# Mainboard_-_Prototyp_2.net
KiCad netlist of a schematic drawn in EAGLE
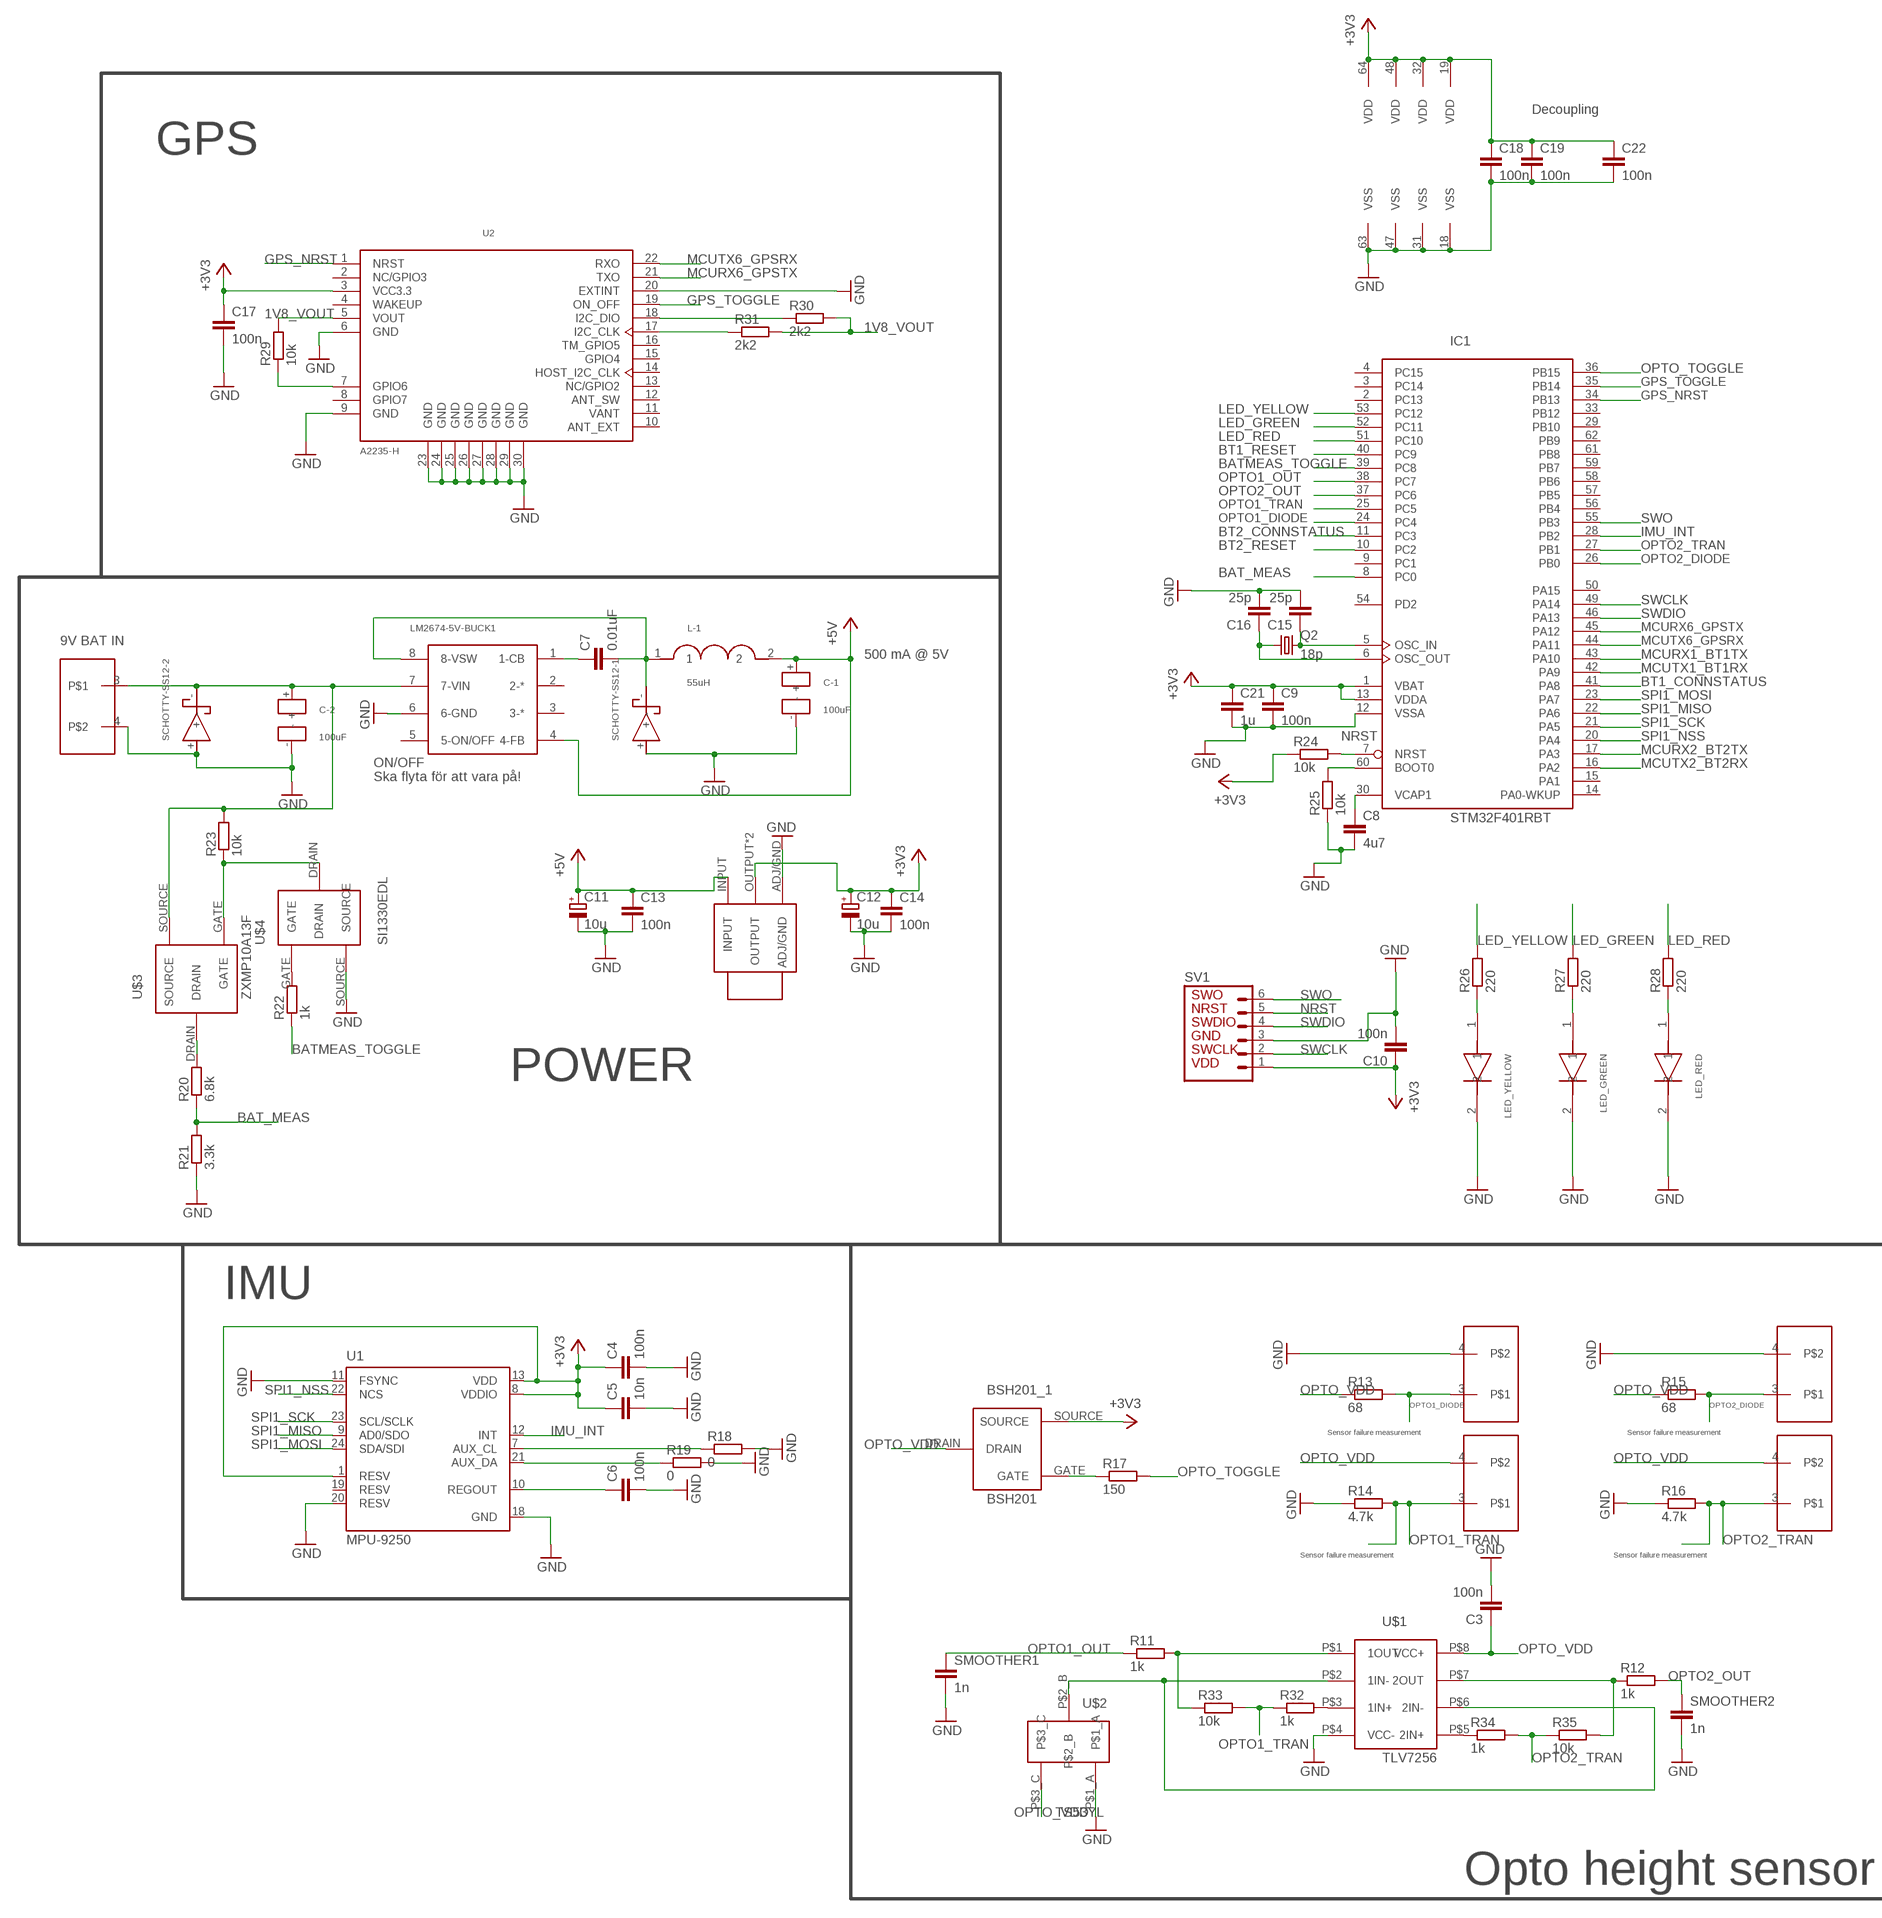
[diagram p0: schematic, sheet 1, part 1 of 2]
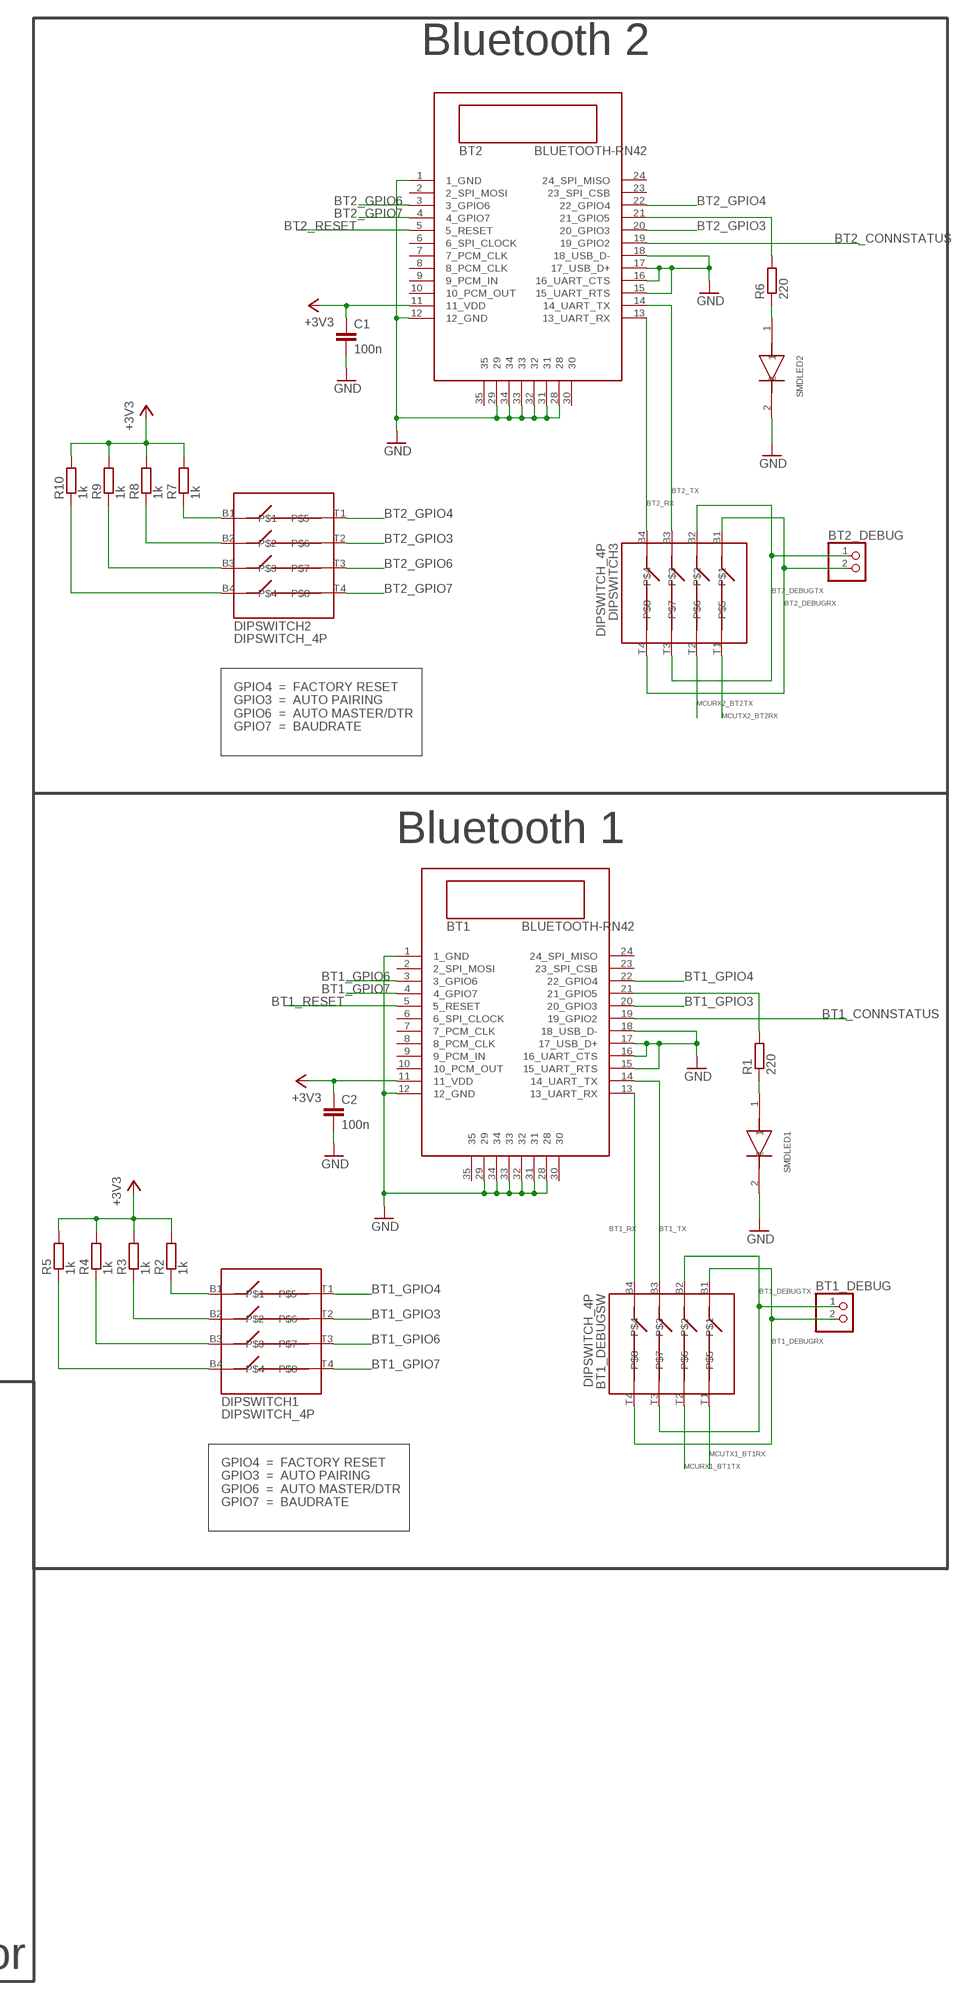
[diagram p1: schematic, sheet 1, part 2 of 2]

(export (version "E")
  (design (tool "Eeschema 10.0.6"))
  (components
    (comp (ref "BSH201_1")
      (value "BSH201")
      (footprint "eagle-import:P-CHANNEL")
      (libsource (lib "eagle-import") (part "BSH201"))
    )
    (comp (ref "BT1")
      (value "BLUETOOTH-RN42")
      (footprint "eagle-import:RN42")
      (libsource (lib "eagle-import") (part "BLUETOOTH-RN42"))
    )
    (comp (ref "BT1_DEBUG")
      (value "PINHD-1X2")
      (footprint "eagle-import:1X02")
      (libsource (lib "eagle-import") (part "PINHD-1X2"))
    )
    (comp (ref "BT1_DEBUGSW")
      (value "DIPSWITCH_4P")
      (footprint "eagle-import:DIPSWITCH4P")
      (libsource (lib "eagle-import") (part "DIPSWITCH_4P"))
    )
    (comp (ref "BT2")
      (value "BLUETOOTH-RN42")
      (footprint "eagle-import:RN42")
      (libsource (lib "eagle-import") (part "BLUETOOTH-RN42"))
    )
    (comp (ref "BT2_DEBUG")
      (value "PINHD-1X2")
      (footprint "eagle-import:1X02")
      (libsource (lib "eagle-import") (part "PINHD-1X2"))
    )
    (comp (ref "C-1")
      (value "100uF")
      (footprint "eagle-import:CAP-6.3MM-DIA")
      (libsource (lib "eagle-import") (part "PANASONIC-CAP"))
    )
    (comp (ref "C-2")
      (value "100uF")
      (footprint "eagle-import:CAP-6.3MM-DIA")
      (libsource (lib "eagle-import") (part "PANASONIC-CAP"))
    )
    (comp (ref "C1")
      (value "100n")
      (footprint "eagle-import:C0805")
      (libsource (lib "eagle-import") (part "C-EUC0805"))
    )
    (comp (ref "C2")
      (value "100n")
      (footprint "eagle-import:C0805")
      (libsource (lib "eagle-import") (part "C-EUC0805"))
    )
    (comp (ref "C3")
      (value "100n")
      (footprint "eagle-import:C0805")
      (libsource (lib "eagle-import") (part "C-EUC0805"))
    )
    (comp (ref "C4")
      (value "100n")
      (footprint "eagle-import:C0805")
      (libsource (lib "eagle-import") (part "C-EUC0805"))
    )
    (comp (ref "C5")
      (value "10n")
      (footprint "eagle-import:C0805")
      (libsource (lib "eagle-import") (part "C-EUC0805"))
    )
    (comp (ref "C6")
      (value "100n")
      (footprint "eagle-import:C0805")
      (libsource (lib "eagle-import") (part "C-EUC0805"))
    )
    (comp (ref "C7")
      (value "0.01uF")
      (footprint "eagle-import:C0805")
      (libsource (lib "eagle-import") (part "C-EUC0805"))
    )
    (comp (ref "C8")
      (value "4u7")
      (footprint "eagle-import:C0805")
      (libsource (lib "eagle-import") (part "C-EUC0805"))
    )
    (comp (ref "C9")
      (value "100n")
      (footprint "eagle-import:C0805")
      (libsource (lib "eagle-import") (part "C-EUC0805"))
    )
    (comp (ref "C10")
      (value "100n")
      (footprint "eagle-import:C0805")
      (libsource (lib "eagle-import") (part "C-EUC0805"))
    )
    (comp (ref "C11")
      (value "10u")
      (footprint "eagle-import:153CLV-0505")
      (libsource (lib "eagle-import") (part "CPOL-EU153CLV-0505"))
    )
    (comp (ref "C12")
      (value "10u")
      (footprint "eagle-import:153CLV-0505")
      (libsource (lib "eagle-import") (part "CPOL-EU153CLV-0505"))
    )
    (comp (ref "C13")
      (value "100n")
      (footprint "eagle-import:C0805")
      (libsource (lib "eagle-import") (part "C-EUC0805"))
    )
    (comp (ref "C14")
      (value "100n")
      (footprint "eagle-import:C0805")
      (libsource (lib "eagle-import") (part "C-EUC0805"))
    )
    (comp (ref "C15")
      (value "25p")
      (footprint "eagle-import:C0805")
      (libsource (lib "eagle-import") (part "C-EUC0805"))
    )
    (comp (ref "C16")
      (value "25p")
      (footprint "eagle-import:C0805")
      (libsource (lib "eagle-import") (part "C-EUC0805"))
    )
    (comp (ref "C17")
      (value "100n")
      (footprint "eagle-import:C0805")
      (libsource (lib "eagle-import") (part "C-EUC0805"))
    )
    (comp (ref "C18")
      (value "100n")
      (footprint "eagle-import:C0805")
      (libsource (lib "eagle-import") (part "C-EUC0805"))
    )
    (comp (ref "C19")
      (value "100n")
      (footprint "eagle-import:C0805")
      (libsource (lib "eagle-import") (part "C-EUC0805"))
    )
    (comp (ref "C21")
      (value "1u")
      (footprint "eagle-import:C0805")
      (libsource (lib "eagle-import") (part "C-EUC0805"))
    )
    (comp (ref "C22")
      (value "100n")
      (footprint "eagle-import:C0805")
      (libsource (lib "eagle-import") (part "C-EUC0805"))
    )
    (comp (ref "DIPSWITCH1")
      (value "DIPSWITCH_4P")
      (footprint "eagle-import:DIPSWITCH4P")
      (libsource (lib "eagle-import") (part "DIPSWITCH_4P"))
    )
    (comp (ref "DIPSWITCH2")
      (value "DIPSWITCH_4P")
      (footprint "eagle-import:DIPSWITCH4P")
      (libsource (lib "eagle-import") (part "DIPSWITCH_4P"))
    )
    (comp (ref "DIPSWITCH3")
      (value "DIPSWITCH_4P")
      (footprint "eagle-import:DIPSWITCH4P")
      (libsource (lib "eagle-import") (part "DIPSWITCH_4P"))
    )
    (comp (ref "IC1")
      (value "STM32F401RBT")
      (footprint "eagle-import:LQFP64")
      (libsource (lib "eagle-import") (part "STM32F401RTB"))
    )
    (comp (ref "L-1")
      (value "55uH")
      (footprint "eagle-import:INDUCTOR")
      (libsource (lib "eagle-import") (part "55UH-INDUKTOR"))
    )
    (comp (ref "LED_GREEN")
      (value "SMD_LED")
      (footprint "eagle-import:SMD_LED_CUSTOM")
      (libsource (lib "eagle-import") (part "SMD_LED"))
    )
    (comp (ref "LED_RED")
      (value "SMD_LED")
      (footprint "eagle-import:SMD_LED_CUSTOM")
      (libsource (lib "eagle-import") (part "SMD_LED"))
    )
    (comp (ref "LED_YELLOW")
      (value "SMD_LED")
      (footprint "eagle-import:SMD_LED_CUSTOM")
      (libsource (lib "eagle-import") (part "SMD_LED"))
    )
    (comp (ref "LM1117-1")
      (value "LM1117")
      (footprint "eagle-import:LM1117")
      (libsource (lib "eagle-import") (part "LM1117"))
    )
    (comp (ref "LM2674-5V-BUCK1")
      (value "LM2674-5VBUCK")
      (footprint "eagle-import:LM2674")
      (libsource (lib "eagle-import") (part "LM2674-5VBUCK"))
    )
    (comp (ref "Q2")
      (value "18p")
      (footprint "eagle-import:HC49UP")
      (libsource (lib "eagle-import") (part "CRYSTALHC49UP"))
    )
    (comp (ref "R1")
      (value "220")
      (footprint "eagle-import:R0805")
      (libsource (lib "eagle-import") (part "resistor_R-EU_R0805"))
    )
    (comp (ref "R2")
      (value "1k")
      (footprint "eagle-import:R0805")
      (libsource (lib "eagle-import") (part "resistor_R-EU_R0805"))
    )
    (comp (ref "R3")
      (value "1k")
      (footprint "eagle-import:R0805")
      (libsource (lib "eagle-import") (part "resistor_R-EU_R0805"))
    )
    (comp (ref "R4")
      (value "1k")
      (footprint "eagle-import:R0805")
      (libsource (lib "eagle-import") (part "resistor_R-EU_R0805"))
    )
    (comp (ref "R5")
      (value "1k")
      (footprint "eagle-import:R0805")
      (libsource (lib "eagle-import") (part "resistor_R-EU_R0805"))
    )
    (comp (ref "R6")
      (value "220")
      (footprint "eagle-import:R0805")
      (libsource (lib "eagle-import") (part "resistor_R-EU_R0805"))
    )
    (comp (ref "R7")
      (value "1k")
      (footprint "eagle-import:R0805")
      (libsource (lib "eagle-import") (part "resistor_R-EU_R0805"))
    )
    (comp (ref "R8")
      (value "1k")
      (footprint "eagle-import:R0805")
      (libsource (lib "eagle-import") (part "resistor_R-EU_R0805"))
    )
    (comp (ref "R9")
      (value "1k")
      (footprint "eagle-import:R0805")
      (libsource (lib "eagle-import") (part "resistor_R-EU_R0805"))
    )
    (comp (ref "R10")
      (value "1k")
      (footprint "eagle-import:R0805")
      (libsource (lib "eagle-import") (part "resistor_R-EU_R0805"))
    )
    (comp (ref "R11")
      (value "1k")
      (footprint "eagle-import:R0805")
      (libsource (lib "eagle-import") (part "R-EU_R0805"))
    )
    (comp (ref "R12")
      (value "1k")
      (footprint "eagle-import:R0805")
      (libsource (lib "eagle-import") (part "R-EU_R0805"))
    )
    (comp (ref "R13")
      (value "68")
      (footprint "eagle-import:R0805")
      (libsource (lib "eagle-import") (part "R-EU_R0805"))
    )
    (comp (ref "R14")
      (value "4.7k")
      (footprint "eagle-import:R0805")
      (libsource (lib "eagle-import") (part "R-EU_R0805"))
    )
    (comp (ref "R15")
      (value "68")
      (footprint "eagle-import:R0805")
      (libsource (lib "eagle-import") (part "R-EU_R0805"))
    )
    (comp (ref "R16")
      (value "4.7k")
      (footprint "eagle-import:R0805")
      (libsource (lib "eagle-import") (part "R-EU_R0805"))
    )
    (comp (ref "R17")
      (value "150")
      (footprint "eagle-import:R0805")
      (libsource (lib "eagle-import") (part "R-EU_R0805"))
    )
    (comp (ref "R18")
      (value "0")
      (footprint "eagle-import:R0805")
      (libsource (lib "eagle-import") (part "R-EU_R0805"))
    )
    (comp (ref "R19")
      (value "0")
      (footprint "eagle-import:R0805")
      (libsource (lib "eagle-import") (part "R-EU_R0805"))
    )
    (comp (ref "R20")
      (value "6.8k")
      (footprint "eagle-import:R0805")
      (libsource (lib "eagle-import") (part "R-EU_R0805"))
    )
    (comp (ref "R21")
      (value "3.3k")
      (footprint "eagle-import:R0805")
      (libsource (lib "eagle-import") (part "R-EU_R0805"))
    )
    (comp (ref "R22")
      (value "1k")
      (footprint "eagle-import:R0805")
      (libsource (lib "eagle-import") (part "R-EU_R0805"))
    )
    (comp (ref "R23")
      (value "10k")
      (footprint "eagle-import:R0805")
      (libsource (lib "eagle-import") (part "R-EU_R0805"))
    )
    (comp (ref "R24")
      (value "10k")
      (footprint "eagle-import:R0805")
      (libsource (lib "eagle-import") (part "R-EU_R0805"))
    )
    (comp (ref "R25")
      (value "10k")
      (footprint "eagle-import:R0805")
      (libsource (lib "eagle-import") (part "R-EU_R0805"))
    )
    (comp (ref "R26")
      (value "220")
      (footprint "eagle-import:R0805")
      (libsource (lib "eagle-import") (part "resistor_R-EU_R0805"))
    )
    (comp (ref "R27")
      (value "220")
      (footprint "eagle-import:R0805")
      (libsource (lib "eagle-import") (part "resistor_R-EU_R0805"))
    )
    (comp (ref "R28")
      (value "220")
      (footprint "eagle-import:R0805")
      (libsource (lib "eagle-import") (part "resistor_R-EU_R0805"))
    )
    (comp (ref "R29")
      (value "10k")
      (footprint "eagle-import:R0805")
      (libsource (lib "eagle-import") (part "R-EU_R0805"))
    )
    (comp (ref "R30")
      (value "2k2")
      (footprint "eagle-import:R0805")
      (libsource (lib "eagle-import") (part "R-EU_R0805"))
    )
    (comp (ref "R31")
      (value "2k2")
      (footprint "eagle-import:R0805")
      (libsource (lib "eagle-import") (part "R-EU_R0805"))
    )
    (comp (ref "R32")
      (value "1k")
      (footprint "eagle-import:R0805")
      (libsource (lib "eagle-import") (part "R-EU_R0805"))
    )
    (comp (ref "R33")
      (value "10k")
      (footprint "eagle-import:R0805")
      (libsource (lib "eagle-import") (part "R-EU_R0805"))
    )
    (comp (ref "R34")
      (value "1k")
      (footprint "eagle-import:R0805")
      (libsource (lib "eagle-import") (part "R-EU_R0805"))
    )
    (comp (ref "R35")
      (value "10k")
      (footprint "eagle-import:R0805")
      (libsource (lib "eagle-import") (part "R-EU_R0805"))
    )
    (comp (ref "SCHOTTY-SS12-1")
      (value "SCHOTTY-SS12")
      (footprint "eagle-import:SCHOTTY")
      (libsource (lib "eagle-import") (part "SCHOTTY-SS12"))
    )
    (comp (ref "SCHOTTY-SS12-2")
      (value "SCHOTTY-SS12")
      (footprint "eagle-import:SCHOTTY")
      (libsource (lib "eagle-import") (part "SCHOTTY-SS12"))
    )
    (comp (ref "SKRUVPLINT_2P1")
      (value "SKRUVPLINT_2P")
      (footprint "eagle-import:SKRUVPLINT_2P")
      (libsource (lib "eagle-import") (part "SKRUVPLINT_2P"))
    )
    (comp (ref "SKRUVPLINT_2P2")
      (value "SKRUVPLINT_2P")
      (footprint "eagle-import:SKRUVPLINT_2P")
      (libsource (lib "eagle-import") (part "SKRUVPLINT_2P"))
    )
    (comp (ref "SKRUVPLINT_2P3")
      (value "SKRUVPLINT_2P")
      (footprint "eagle-import:SKRUVPLINT_2P")
      (libsource (lib "eagle-import") (part "SKRUVPLINT_2P"))
    )
    (comp (ref "SKRUVPLINT_2P4")
      (value "SKRUVPLINT_2P")
      (footprint "eagle-import:SKRUVPLINT_2P")
      (libsource (lib "eagle-import") (part "SKRUVPLINT_2P"))
    )
    (comp (ref "SKRUVPLINT_2P5")
      (value "SKRUVPLINT_2P")
      (footprint "eagle-import:SKRUVPLINT_2P")
      (libsource (lib "eagle-import") (part "SKRUVPLINT_2P"))
    )
    (comp (ref "SMDLED1")
      (value "SMD_LED")
      (footprint "eagle-import:SMD_LED_CUSTOM")
      (libsource (lib "eagle-import") (part "SMD_LED"))
    )
    (comp (ref "SMDLED2")
      (value "SMD_LED")
      (footprint "eagle-import:SMD_LED_CUSTOM")
      (libsource (lib "eagle-import") (part "SMD_LED"))
    )
    (comp (ref "SMOOTHER1")
      (value "1n")
      (footprint "eagle-import:C0805")
      (libsource (lib "eagle-import") (part "C-EUC0805"))
    )
    (comp (ref "SMOOTHER2")
      (value "1n")
      (footprint "eagle-import:C0805")
      (libsource (lib "eagle-import") (part "C-EUC0805"))
    )
    (comp (ref "SV1")
      (value "MA06-1")
      (footprint "eagle-import:MA06-1")
      (libsource (lib "eagle-import") (part "MA06-1"))
    )
    (comp (ref "U$1")
      (value "TLV7256")
      (footprint "eagle-import:VSSOP")
      (libsource (lib "eagle-import") (part "TLV7256"))
    )
    (comp (ref "U$2")
      (value "TS53YL")
      (footprint "eagle-import:POT")
      (libsource (lib "eagle-import") (part "TS53YL"))
    )
    (comp (ref "U$3")
      (value "ZXMP10A13F")
      (footprint "eagle-import:P-CHANNEL")
      (libsource (lib "eagle-import") (part "ZXMP10A13F"))
    )
    (comp (ref "U$4")
      (value "SI1330EDL")
      (footprint "eagle-import:SOT-323")
      (libsource (lib "eagle-import") (part "SI1330EDL"))
    )
    (comp (ref "U1")
      (value "MPU-9250")
      (footprint "eagle-import:QFN40P300X300X105-25N")
      (fields (field (name "MF") "InvenSense"))
      (libsource (lib "eagle-import") (part "MPU-9250"))
    )
    (comp (ref "U2")
      (value "A2235-H")
      (footprint "eagle-import:XCVR_A2235-H")
      (fields (field (name "MF") "Maestro Wireless") (field (name "MP") "A2235H"))
      (libsource (lib "eagle-import") (part "A2235-H"))
    )
  )
  (nets
    (net (code "1") (name "+3V3") (class "Default")
      (node (ref "BSH201_1") (pin "SOURCE") (pinfunction "SOURCE_SOURCE") (pintype "bidirectional"))
      (node (ref "BT1") (pin "11") (pinfunction "11_VDD_11") (pintype "bidirectional"))
      (node (ref "BT2") (pin "11") (pinfunction "11_VDD_11") (pintype "bidirectional"))
      (node (ref "C1") (pin "1") (pinfunction "1_1") (pintype "passive"))
      (node (ref "C10") (pin "1") (pinfunction "1_1") (pintype "passive"))
      (node (ref "C12") (pin "+") (pinfunction "+_+") (pintype "passive"))
      (node (ref "C14") (pin "1") (pinfunction "1_1") (pintype "passive"))
      (node (ref "C17") (pin "1") (pinfunction "1_1") (pintype "passive"))
      (node (ref "C18") (pin "1") (pinfunction "1_1") (pintype "passive"))
      (node (ref "C19") (pin "1") (pinfunction "1_1") (pintype "passive"))
      (node (ref "C2") (pin "1") (pinfunction "1_1") (pintype "passive"))
      (node (ref "C21") (pin "1") (pinfunction "1_1") (pintype "passive"))
      (node (ref "C22") (pin "1") (pinfunction "1_1") (pintype "passive"))
      (node (ref "C4") (pin "1") (pinfunction "1_1") (pintype "passive"))
      (node (ref "C5") (pin "1") (pinfunction "1_1") (pintype "passive"))
      (node (ref "C9") (pin "1") (pinfunction "1_1") (pintype "passive"))
      (node (ref "IC1") (pin "1") (pinfunction "VBAT_1") (pintype "power_in"))
      (node (ref "IC1") (pin "13") (pinfunction "VDDA_13") (pintype "power_in"))
      (node (ref "IC1") (pin "19") (pinfunction "VDD_19") (pintype "power_in"))
      (node (ref "IC1") (pin "32") (pinfunction "VDD_32") (pintype "power_in"))
      (node (ref "IC1") (pin "48") (pinfunction "VDD_48") (pintype "power_in"))
      (node (ref "IC1") (pin "64") (pinfunction "VDD_64") (pintype "power_in"))
      (node (ref "LM1117-1") (pin "OUTPUT") (pinfunction "OUTPUT_OUTPUT") (pintype "bidirectional"))
      (node (ref "LM1117-1") (pin "OUTPUT2") (pinfunction "OUTPUT_OUTPUT2") (pintype "bidirectional"))
      (node (ref "R10") (pin "2") (pinfunction "2_2") (pintype "passive"))
      (node (ref "R2") (pin "2") (pinfunction "2_2") (pintype "passive"))
      (node (ref "R24") (pin "1") (pinfunction "1_1") (pintype "passive"))
      (node (ref "R3") (pin "2") (pinfunction "2_2") (pintype "passive"))
      (node (ref "R4") (pin "2") (pinfunction "2_2") (pintype "passive"))
      (node (ref "R5") (pin "2") (pinfunction "2_2") (pintype "passive"))
      (node (ref "R7") (pin "2") (pinfunction "2_2") (pintype "passive"))
      (node (ref "R8") (pin "2") (pinfunction "2_2") (pintype "passive"))
      (node (ref "R9") (pin "2") (pinfunction "2_2") (pintype "passive"))
      (node (ref "SV1") (pin "1") (pinfunction "1_1") (pintype "passive"))
      (node (ref "U1") (pin "1") (pinfunction "RESV_1") (pintype "power_in"))
      (node (ref "U1") (pin "13") (pinfunction "VDD_13") (pintype "power_in"))
      (node (ref "U1") (pin "8") (pinfunction "VDDIO_8") (pintype "power_in"))
      (node (ref "U2") (pin "3") (pinfunction "VCC3.3_3") (pintype "power_in"))
    )
    (net (code "2") (name "+5V") (class "Default")
      (node (ref "C-1") (pin "+") (pinfunction "+_+") (pintype "bidirectional"))
      (node (ref "C11") (pin "+") (pinfunction "+_+") (pintype "passive"))
      (node (ref "C13") (pin "1") (pinfunction "1_1") (pintype "passive"))
      (node (ref "L-1") (pin "2") (pinfunction "2_2") (pintype "bidirectional"))
      (node (ref "LM1117-1") (pin "INPUT") (pinfunction "INPUT_INPUT") (pintype "bidirectional"))
      (node (ref "LM2674-5V-BUCK1") (pin "4") (pinfunction "4-FB_4") (pintype "bidirectional"))
    )
    (net (code "3") (name "/1V8_VOUT") (class "Default")
      (node (ref "R29") (pin "2") (pinfunction "2_2") (pintype "passive"))
      (node (ref "R30") (pin "2") (pinfunction "2_2") (pintype "passive"))
      (node (ref "R31") (pin "2") (pinfunction "2_2") (pintype "passive"))
      (node (ref "U2") (pin "5") (pinfunction "VOUT_5") (pintype "output"))
    )
    (net (code "4") (name "/BATMEAS_TOGGLE") (class "Default")
      (node (ref "IC1") (pin "39") (pinfunction "PC8_39") (pintype "bidirectional"))
      (node (ref "R22") (pin "1") (pinfunction "1_1") (pintype "passive"))
    )
    (net (code "5") (name "/BAT_MEAS") (class "Default")
      (node (ref "IC1") (pin "8") (pinfunction "PC0_8") (pintype "bidirectional"))
      (node (ref "R20") (pin "1") (pinfunction "1_1") (pintype "passive"))
      (node (ref "R21") (pin "2") (pinfunction "2_2") (pintype "passive"))
    )
    (net (code "6") (name "/BT1_CONNSTATUS") (class "Default")
      (node (ref "BT1") (pin "19") (pinfunction "19_GPIO2_19") (pintype "bidirectional"))
      (node (ref "IC1") (pin "41") (pinfunction "PA8_41") (pintype "bidirectional"))
    )
    (net (code "7") (name "/BT1_DEBUGRX") (class "Default")
      (node (ref "BT1_DEBUG") (pin "2") (pinfunction "2_2") (pintype "passive"))
      (node (ref "BT1_DEBUGSW") (pin "B1") (pinfunction "P$1_B1") (pintype "bidirectional"))
      (node (ref "BT1_DEBUGSW") (pin "T4") (pinfunction "P$8_T4") (pintype "bidirectional"))
    )
    (net (code "8") (name "/BT1_DEBUGTX") (class "Default")
      (node (ref "BT1_DEBUG") (pin "1") (pinfunction "1_1") (pintype "passive"))
      (node (ref "BT1_DEBUGSW") (pin "B2") (pinfunction "P$2_B2") (pintype "bidirectional"))
      (node (ref "BT1_DEBUGSW") (pin "T3") (pinfunction "P$7_T3") (pintype "bidirectional"))
    )
    (net (code "9") (name "/BT1_GPIO3") (class "Default")
      (node (ref "BT1") (pin "20") (pinfunction "20_GPIO3_20") (pintype "bidirectional"))
      (node (ref "DIPSWITCH1") (pin "T2") (pinfunction "P$6_T2") (pintype "bidirectional"))
    )
    (net (code "10") (name "/BT1_GPIO4") (class "Default")
      (node (ref "BT1") (pin "22") (pinfunction "22_GPIO4_22") (pintype "bidirectional"))
      (node (ref "DIPSWITCH1") (pin "T1") (pinfunction "P$5_T1") (pintype "bidirectional"))
    )
    (net (code "11") (name "/BT1_GPIO6") (class "Default")
      (node (ref "BT1") (pin "3") (pinfunction "3_GPIO6_3") (pintype "bidirectional"))
      (node (ref "DIPSWITCH1") (pin "T3") (pinfunction "P$7_T3") (pintype "bidirectional"))
    )
    (net (code "12") (name "/BT1_GPIO7") (class "Default")
      (node (ref "BT1") (pin "4") (pinfunction "4_GPIO7_4") (pintype "bidirectional"))
      (node (ref "DIPSWITCH1") (pin "T4") (pinfunction "P$8_T4") (pintype "bidirectional"))
    )
    (net (code "13") (name "/BT1_RESET") (class "Default")
      (node (ref "BT1") (pin "5") (pinfunction "5_RESET_5") (pintype "bidirectional"))
      (node (ref "IC1") (pin "40") (pinfunction "PC9_40") (pintype "bidirectional"))
    )
    (net (code "14") (name "/BT1_RX") (class "Default")
      (node (ref "BT1") (pin "13") (pinfunction "13_UART_RX_13") (pintype "bidirectional"))
      (node (ref "BT1_DEBUGSW") (pin "B4") (pinfunction "P$4_B4") (pintype "bidirectional"))
    )
    (net (code "15") (name "/BT1_TX") (class "Default")
      (node (ref "BT1") (pin "14") (pinfunction "14_UART_TX_14") (pintype "bidirectional"))
      (node (ref "BT1_DEBUGSW") (pin "B3") (pinfunction "P$3_B3") (pintype "bidirectional"))
    )
    (net (code "16") (name "/BT2_CONNSTATUS") (class "Default")
      (node (ref "BT2") (pin "19") (pinfunction "19_GPIO2_19") (pintype "bidirectional"))
      (node (ref "IC1") (pin "11") (pinfunction "PC3_11") (pintype "bidirectional"))
    )
    (net (code "17") (name "/BT2_DEBUGRX") (class "Default")
      (node (ref "BT2_DEBUG") (pin "2") (pinfunction "2_2") (pintype "passive"))
      (node (ref "DIPSWITCH3") (pin "B1") (pinfunction "P$1_B1") (pintype "bidirectional"))
      (node (ref "DIPSWITCH3") (pin "T4") (pinfunction "P$8_T4") (pintype "bidirectional"))
    )
    (net (code "18") (name "/BT2_DEBUGTX") (class "Default")
      (node (ref "BT2_DEBUG") (pin "1") (pinfunction "1_1") (pintype "passive"))
      (node (ref "DIPSWITCH3") (pin "B2") (pinfunction "P$2_B2") (pintype "bidirectional"))
      (node (ref "DIPSWITCH3") (pin "T3") (pinfunction "P$7_T3") (pintype "bidirectional"))
    )
    (net (code "19") (name "/BT2_GPIO3") (class "Default")
      (node (ref "BT2") (pin "20") (pinfunction "20_GPIO3_20") (pintype "bidirectional"))
      (node (ref "DIPSWITCH2") (pin "T2") (pinfunction "P$6_T2") (pintype "bidirectional"))
    )
    (net (code "20") (name "/BT2_GPIO4") (class "Default")
      (node (ref "BT2") (pin "22") (pinfunction "22_GPIO4_22") (pintype "bidirectional"))
      (node (ref "DIPSWITCH2") (pin "T1") (pinfunction "P$5_T1") (pintype "bidirectional"))
    )
    (net (code "21") (name "/BT2_GPIO6") (class "Default")
      (node (ref "BT2") (pin "3") (pinfunction "3_GPIO6_3") (pintype "bidirectional"))
      (node (ref "DIPSWITCH2") (pin "T3") (pinfunction "P$7_T3") (pintype "bidirectional"))
    )
    (net (code "22") (name "/BT2_GPIO7") (class "Default")
      (node (ref "BT2") (pin "4") (pinfunction "4_GPIO7_4") (pintype "bidirectional"))
      (node (ref "DIPSWITCH2") (pin "T4") (pinfunction "P$8_T4") (pintype "bidirectional"))
    )
    (net (code "23") (name "/BT2_RESET") (class "Default")
      (node (ref "BT2") (pin "5") (pinfunction "5_RESET_5") (pintype "bidirectional"))
      (node (ref "IC1") (pin "10") (pinfunction "PC2_10") (pintype "bidirectional"))
    )
    (net (code "24") (name "/BT2_RX") (class "Default")
      (node (ref "BT2") (pin "13") (pinfunction "13_UART_RX_13") (pintype "bidirectional"))
      (node (ref "DIPSWITCH3") (pin "B4") (pinfunction "P$4_B4") (pintype "bidirectional"))
    )
    (net (code "25") (name "/BT2_TX") (class "Default")
      (node (ref "BT2") (pin "14") (pinfunction "14_UART_TX_14") (pintype "bidirectional"))
      (node (ref "DIPSWITCH3") (pin "B3") (pinfunction "P$3_B3") (pintype "bidirectional"))
    )
    (net (code "26") (name "/GPS_NRST") (class "Default")
      (node (ref "IC1") (pin "34") (pinfunction "PB13_34") (pintype "bidirectional"))
      (node (ref "U2") (pin "1") (pinfunction "NRST_1") (pintype "input"))
    )
    (net (code "27") (name "/GPS_TOGGLE") (class "Default")
      (node (ref "IC1") (pin "35") (pinfunction "PB14_35") (pintype "bidirectional"))
      (node (ref "U2") (pin "19") (pinfunction "ON_OFF_19") (pintype "input"))
    )
    (net (code "28") (name "/IMU_INT") (class "Default")
      (node (ref "IC1") (pin "28") (pinfunction "PB2_28") (pintype "bidirectional"))
      (node (ref "U1") (pin "12") (pinfunction "INT_12") (pintype "output"))
    )
    (net (code "29") (name "/LED_GREEN") (class "Default")
      (node (ref "IC1") (pin "52") (pinfunction "PC11_52") (pintype "bidirectional"))
      (node (ref "R27") (pin "2") (pinfunction "2_2") (pintype "passive"))
    )
    (net (code "30") (name "/LED_RED") (class "Default")
      (node (ref "IC1") (pin "51") (pinfunction "PC10_51") (pintype "bidirectional"))
      (node (ref "R28") (pin "2") (pinfunction "2_2") (pintype "passive"))
    )
    (net (code "31") (name "/LED_YELLOW") (class "Default")
      (node (ref "IC1") (pin "53") (pinfunction "PC12_53") (pintype "bidirectional"))
      (node (ref "R26") (pin "2") (pinfunction "2_2") (pintype "passive"))
    )
    (net (code "32") (name "/MCURX1_BT1TX") (class "Default")
      (node (ref "BT1_DEBUGSW") (pin "T2") (pinfunction "P$6_T2") (pintype "bidirectional"))
      (node (ref "IC1") (pin "43") (pinfunction "PA10_43") (pintype "bidirectional"))
    )
    (net (code "33") (name "/MCURX2_BT2TX") (class "Default")
      (node (ref "DIPSWITCH3") (pin "T2") (pinfunction "P$6_T2") (pintype "bidirectional"))
      (node (ref "IC1") (pin "17") (pinfunction "PA3_17") (pintype "bidirectional"))
    )
    (net (code "34") (name "/MCURX6_GPSTX") (class "Default")
      (node (ref "IC1") (pin "45") (pinfunction "PA12_45") (pintype "bidirectional"))
      (node (ref "U2") (pin "21") (pinfunction "TXO_21") (pintype "output"))
    )
    (net (code "35") (name "/MCUTX1_BT1RX") (class "Default")
      (node (ref "BT1_DEBUGSW") (pin "T1") (pinfunction "P$5_T1") (pintype "bidirectional"))
      (node (ref "IC1") (pin "42") (pinfunction "PA9_42") (pintype "bidirectional"))
    )
    (net (code "36") (name "/MCUTX2_BT2RX") (class "Default")
      (node (ref "DIPSWITCH3") (pin "T1") (pinfunction "P$5_T1") (pintype "bidirectional"))
      (node (ref "IC1") (pin "16") (pinfunction "PA2_16") (pintype "bidirectional"))
    )
    (net (code "37") (name "/MCUTX6_GPSRX") (class "Default")
      (node (ref "IC1") (pin "44") (pinfunction "PA11_44") (pintype "bidirectional"))
      (node (ref "U2") (pin "22") (pinfunction "RXO_22") (pintype "input"))
    )
    (net (code "38") (name "/NRST") (class "Default")
      (node (ref "IC1") (pin "7") (pinfunction "NRST_7") (pintype "bidirectional"))
      (node (ref "R24") (pin "2") (pinfunction "2_2") (pintype "passive"))
      (node (ref "SV1") (pin "5") (pinfunction "5_5") (pintype "passive"))
    )
    (net (code "39") (name "/OPTO1_DIODE") (class "Default")
      (node (ref "IC1") (pin "24") (pinfunction "PC4_24") (pintype "bidirectional"))
      (node (ref "R13") (pin "2") (pinfunction "2_2") (pintype "passive"))
      (node (ref "SKRUVPLINT_2P1") (pin "3") (pinfunction "P$1_3") (pintype "bidirectional"))
    )
    (net (code "40") (name "/OPTO1_OUT") (class "Default")
      (node (ref "IC1") (pin "38") (pinfunction "PC7_38") (pintype "bidirectional"))
      (node (ref "R11") (pin "1") (pinfunction "1_1") (pintype "passive"))
      (node (ref "SMOOTHER1") (pin "1") (pinfunction "1_1") (pintype "passive"))
    )
    (net (code "41") (name "/OPTO1_TRAN") (class "Default")
      (node (ref "IC1") (pin "25") (pinfunction "PC5_25") (pintype "bidirectional"))
      (node (ref "R14") (pin "2") (pinfunction "2_2") (pintype "passive"))
      (node (ref "R32") (pin "1") (pinfunction "1_1") (pintype "passive"))
      (node (ref "R33") (pin "2") (pinfunction "2_2") (pintype "passive"))
      (node (ref "SKRUVPLINT_2P2") (pin "3") (pinfunction "P$1_3") (pintype "bidirectional"))
    )
    (net (code "42") (name "/OPTO2_DIODE") (class "Default")
      (node (ref "IC1") (pin "26") (pinfunction "PB0_26") (pintype "bidirectional"))
      (node (ref "R15") (pin "2") (pinfunction "2_2") (pintype "passive"))
      (node (ref "SKRUVPLINT_2P3") (pin "3") (pinfunction "P$1_3") (pintype "bidirectional"))
    )
    (net (code "43") (name "/OPTO2_OUT") (class "Default")
      (node (ref "IC1") (pin "37") (pinfunction "PC6_37") (pintype "bidirectional"))
      (node (ref "R12") (pin "2") (pinfunction "2_2") (pintype "passive"))
      (node (ref "SMOOTHER2") (pin "1") (pinfunction "1_1") (pintype "passive"))
    )
    (net (code "44") (name "/OPTO2_TRAN") (class "Default")
      (node (ref "IC1") (pin "27") (pinfunction "PB1_27") (pintype "bidirectional"))
      (node (ref "R16") (pin "2") (pinfunction "2_2") (pintype "passive"))
      (node (ref "R34") (pin "2") (pinfunction "2_2") (pintype "passive"))
      (node (ref "R35") (pin "1") (pinfunction "1_1") (pintype "passive"))
      (node (ref "SKRUVPLINT_2P4") (pin "3") (pinfunction "P$1_3") (pintype "bidirectional"))
    )
    (net (code "45") (name "/OPTO_TOGGLE") (class "Default")
      (node (ref "IC1") (pin "36") (pinfunction "PB15_36") (pintype "bidirectional"))
      (node (ref "R17") (pin "2") (pinfunction "2_2") (pintype "passive"))
    )
    (net (code "46") (name "/OPTO_VDD") (class "Default")
      (node (ref "BSH201_1") (pin "DRAIN") (pinfunction "DRAIN_DRAIN") (pintype "bidirectional"))
      (node (ref "C3") (pin "1") (pinfunction "1_1") (pintype "passive"))
      (node (ref "R13") (pin "1") (pinfunction "1_1") (pintype "passive"))
      (node (ref "R15") (pin "1") (pinfunction "1_1") (pintype "passive"))
      (node (ref "SKRUVPLINT_2P2") (pin "4") (pinfunction "P$2_4") (pintype "bidirectional"))
      (node (ref "SKRUVPLINT_2P4") (pin "4") (pinfunction "P$2_4") (pintype "bidirectional"))
      (node (ref "U$1") (pin "P$8") (pinfunction "VCC+_P$8") (pintype "bidirectional"))
      (node (ref "U$2") (pin "P$3_C") (pinfunction "P$3_C_P$3_C") (pintype "bidirectional"))
    )
    (net (code "47") (name "/RESV") (class "Default")
      (node (ref "U1") (pin "19") (pinfunction "RESV_19") (pintype "power_in"))
    )
    (net (code "48") (name "/SPI1_MISO") (class "Default")
      (node (ref "IC1") (pin "22") (pinfunction "PA6_22") (pintype "bidirectional"))
      (node (ref "U1") (pin "9") (pinfunction "AD0/SDO_9") (pintype "bidirectional"))
    )
    (net (code "49") (name "/SPI1_MOSI") (class "Default")
      (node (ref "IC1") (pin "23") (pinfunction "PA7_23") (pintype "bidirectional"))
      (node (ref "U1") (pin "24") (pinfunction "SDA/SDI_24") (pintype "bidirectional"))
    )
    (net (code "50") (name "/SPI1_NSS") (class "Default")
      (node (ref "IC1") (pin "20") (pinfunction "PA4_20") (pintype "bidirectional"))
      (node (ref "U1") (pin "22") (pinfunction "NCS_22") (pintype "input"))
    )
    (net (code "51") (name "/SPI1_SCK") (class "Default")
      (node (ref "IC1") (pin "21") (pinfunction "PA5_21") (pintype "bidirectional"))
      (node (ref "U1") (pin "23") (pinfunction "SCL/SCLK_23") (pintype "input"))
    )
    (net (code "52") (name "/SWCLK") (class "Default")
      (node (ref "IC1") (pin "49") (pinfunction "PA14_49") (pintype "bidirectional"))
      (node (ref "SV1") (pin "2") (pinfunction "2_2") (pintype "passive"))
    )
    (net (code "53") (name "/SWDIO") (class "Default")
      (node (ref "IC1") (pin "46") (pinfunction "PA13_46") (pintype "bidirectional"))
      (node (ref "SV1") (pin "4") (pinfunction "4_4") (pintype "passive"))
    )
    (net (code "54") (name "/SWO") (class "Default")
      (node (ref "IC1") (pin "55") (pinfunction "PB3_55") (pintype "bidirectional"))
      (node (ref "SV1") (pin "6") (pinfunction "6_6") (pintype "passive"))
    )
    (net (code "55") (name "/VANT") (class "Default")
      (node (ref "U2") (pin "11") (pinfunction "VANT_11") (pintype "power_in"))
    )
    (net (code "56") (name "GND") (class "Default")
      (node (ref "BT1") (pin "1") (pinfunction "1_GND_1") (pintype "bidirectional"))
      (node (ref "BT1") (pin "12") (pinfunction "12_GND_12") (pintype "bidirectional"))
      (node (ref "BT1") (pin "15") (pinfunction "15_UART_RTS_15") (pintype "bidirectional"))
      (node (ref "BT1") (pin "16") (pinfunction "16_UART_CTS_16") (pintype "bidirectional"))
      (node (ref "BT1") (pin "17") (pinfunction "17_USB_D+_17") (pintype "bidirectional"))
      (node (ref "BT1") (pin "18") (pinfunction "18_USB_D-_18") (pintype "bidirectional"))
      (node (ref "BT1") (pin "28") (pinfunction "28_28") (pintype "bidirectional"))
      (node (ref "BT1") (pin "29") (pinfunction "29_29") (pintype "bidirectional"))
      (node (ref "BT1") (pin "31") (pinfunction "31_31") (pintype "bidirectional"))
      (node (ref "BT1") (pin "32") (pinfunction "32_32") (pintype "bidirectional"))
      (node (ref "BT1") (pin "33") (pinfunction "33_33") (pintype "bidirectional"))
      (node (ref "BT1") (pin "34") (pinfunction "34_34") (pintype "bidirectional"))
      (node (ref "BT2") (pin "1") (pinfunction "1_GND_1") (pintype "bidirectional"))
      (node (ref "BT2") (pin "12") (pinfunction "12_GND_12") (pintype "bidirectional"))
      (node (ref "BT2") (pin "15") (pinfunction "15_UART_RTS_15") (pintype "bidirectional"))
      (node (ref "BT2") (pin "16") (pinfunction "16_UART_CTS_16") (pintype "bidirectional"))
      (node (ref "BT2") (pin "17") (pinfunction "17_USB_D+_17") (pintype "bidirectional"))
      (node (ref "BT2") (pin "18") (pinfunction "18_USB_D-_18") (pintype "bidirectional"))
      (node (ref "BT2") (pin "28") (pinfunction "28_28") (pintype "bidirectional"))
      (node (ref "BT2") (pin "29") (pinfunction "29_29") (pintype "bidirectional"))
      (node (ref "BT2") (pin "31") (pinfunction "31_31") (pintype "bidirectional"))
      (node (ref "BT2") (pin "32") (pinfunction "32_32") (pintype "bidirectional"))
      (node (ref "BT2") (pin "33") (pinfunction "33_33") (pintype "bidirectional"))
      (node (ref "BT2") (pin "34") (pinfunction "34_34") (pintype "bidirectional"))
      (node (ref "C-1") (pin "-") (pinfunction "-_-") (pintype "bidirectional"))
      (node (ref "C-2") (pin "-") (pinfunction "-_-") (pintype "bidirectional"))
      (node (ref "C1") (pin "2") (pinfunction "2_2") (pintype "passive"))
      (node (ref "C10") (pin "2") (pinfunction "2_2") (pintype "passive"))
      (node (ref "C11") (pin "-") (pinfunction "-_-") (pintype "passive"))
      (node (ref "C12") (pin "-") (pinfunction "-_-") (pintype "passive"))
      (node (ref "C13") (pin "2") (pinfunction "2_2") (pintype "passive"))
      (node (ref "C14") (pin "2") (pinfunction "2_2") (pintype "passive"))
      (node (ref "C15") (pin "2") (pinfunction "2_2") (pintype "passive"))
      (node (ref "C16") (pin "2") (pinfunction "2_2") (pintype "passive"))
      (node (ref "C17") (pin "2") (pinfunction "2_2") (pintype "passive"))
      (node (ref "C18") (pin "2") (pinfunction "2_2") (pintype "passive"))
      (node (ref "C19") (pin "2") (pinfunction "2_2") (pintype "passive"))
      (node (ref "C2") (pin "2") (pinfunction "2_2") (pintype "passive"))
      (node (ref "C21") (pin "2") (pinfunction "2_2") (pintype "passive"))
      (node (ref "C22") (pin "2") (pinfunction "2_2") (pintype "passive"))
      (node (ref "C3") (pin "2") (pinfunction "2_2") (pintype "passive"))
      (node (ref "C4") (pin "2") (pinfunction "2_2") (pintype "passive"))
      (node (ref "C5") (pin "2") (pinfunction "2_2") (pintype "passive"))
      (node (ref "C6") (pin "2") (pinfunction "2_2") (pintype "passive"))
      (node (ref "C8") (pin "2") (pinfunction "2_2") (pintype "passive"))
      (node (ref "C9") (pin "2") (pinfunction "2_2") (pintype "passive"))
      (node (ref "IC1") (pin "12") (pinfunction "VSSA_12") (pintype "power_in"))
      (node (ref "IC1") (pin "18") (pinfunction "VSS_18") (pintype "power_in"))
      (node (ref "IC1") (pin "31") (pinfunction "VSS_31") (pintype "power_in"))
      (node (ref "IC1") (pin "47") (pinfunction "VSS_47") (pintype "power_in"))
      (node (ref "IC1") (pin "63") (pinfunction "VSS_63") (pintype "power_in"))
      (node (ref "LED_GREEN") (pin "2") (pinfunction "2_2") (pintype "bidirectional"))
      (node (ref "LED_RED") (pin "2") (pinfunction "2_2") (pintype "bidirectional"))
      (node (ref "LED_YELLOW") (pin "2") (pinfunction "2_2") (pintype "bidirectional"))
      (node (ref "LM1117-1") (pin "ADJ/GND") (pinfunction "ADJ/GND_ADJ/GND") (pintype "bidirectional"))
      (node (ref "LM2674-5V-BUCK1") (pin "6") (pinfunction "6-GND_6") (pintype "bidirectional"))
      (node (ref "R14") (pin "1") (pinfunction "1_1") (pintype "passive"))
      (node (ref "R16") (pin "1") (pinfunction "1_1") (pintype "passive"))
      (node (ref "R18") (pin "2") (pinfunction "2_2") (pintype "passive"))
      (node (ref "R19") (pin "2") (pinfunction "2_2") (pintype "passive"))
      (node (ref "R21") (pin "1") (pinfunction "1_1") (pintype "passive"))
      (node (ref "R25") (pin "1") (pinfunction "1_1") (pintype "passive"))
      (node (ref "SCHOTTY-SS12-1") (pin "+") (pinfunction "+_+") (pintype "bidirectional"))
      (node (ref "SCHOTTY-SS12-2") (pin "+") (pinfunction "+_+") (pintype "bidirectional"))
      (node (ref "SKRUVPLINT_2P1") (pin "4") (pinfunction "P$2_4") (pintype "bidirectional"))
      (node (ref "SKRUVPLINT_2P3") (pin "4") (pinfunction "P$2_4") (pintype "bidirectional"))
      (node (ref "SKRUVPLINT_2P5") (pin "4") (pinfunction "P$2_4") (pintype "bidirectional"))
      (node (ref "SMDLED1") (pin "2") (pinfunction "2_2") (pintype "bidirectional"))
      (node (ref "SMDLED2") (pin "2") (pinfunction "2_2") (pintype "bidirectional"))
      (node (ref "SMOOTHER1") (pin "2") (pinfunction "2_2") (pintype "passive"))
      (node (ref "SMOOTHER2") (pin "2") (pinfunction "2_2") (pintype "passive"))
      (node (ref "SV1") (pin "3") (pinfunction "3_3") (pintype "passive"))
      (node (ref "U$1") (pin "P$4") (pinfunction "VCC-_P$4") (pintype "bidirectional"))
      (node (ref "U$2") (pin "P$1_A") (pinfunction "P$1_A_P$1_A") (pintype "bidirectional"))
      (node (ref "U$4") (pin "SOURCE") (pinfunction "SOURCE_SOURCE") (pintype "bidirectional"))
      (node (ref "U1") (pin "11") (pinfunction "FSYNC_11") (pintype "input"))
      (node (ref "U1") (pin "18") (pinfunction "GND_18") (pintype "power_in"))
      (node (ref "U1") (pin "20") (pinfunction "RESV_20") (pintype "power_in"))
      (node (ref "U2") (pin "20") (pinfunction "EXTINT_20") (pintype "input"))
      (node (ref "U2") (pin "23") (pinfunction "GND_23") (pintype "power_in"))
      (node (ref "U2") (pin "24") (pinfunction "GND_24") (pintype "power_in"))
      (node (ref "U2") (pin "25") (pinfunction "GND_25") (pintype "power_in"))
      (node (ref "U2") (pin "26") (pinfunction "GND_26") (pintype "power_in"))
      (node (ref "U2") (pin "27") (pinfunction "GND_27") (pintype "power_in"))
      (node (ref "U2") (pin "28") (pinfunction "GND_28") (pintype "power_in"))
      (node (ref "U2") (pin "29") (pinfunction "GND_29") (pintype "power_in"))
      (node (ref "U2") (pin "30") (pinfunction "GND_30") (pintype "power_in"))
      (node (ref "U2") (pin "6") (pinfunction "GND_6") (pintype "power_in"))
      (node (ref "U2") (pin "9") (pinfunction "GND_9") (pintype "power_in"))
    )
    (net (code "57") (name "Net-(BSH201_1-PadGATE)") (class "Default")
      (node (ref "BSH201_1") (pin "GATE") (pinfunction "GATE_GATE") (pintype "bidirectional"))
      (node (ref "R17") (pin "1") (pinfunction "1_1") (pintype "passive"))
    )
    (net (code "58") (name "Net-(BT1-21_GPIO5)") (class "Default")
      (node (ref "BT1") (pin "21") (pinfunction "21_GPIO5_21") (pintype "bidirectional"))
      (node (ref "R1") (pin "2") (pinfunction "2_2") (pintype "passive"))
    )
    (net (code "59") (name "Net-(BT2-21_GPIO5)") (class "Default")
      (node (ref "BT2") (pin "21") (pinfunction "21_GPIO5_21") (pintype "bidirectional"))
      (node (ref "R6") (pin "2") (pinfunction "2_2") (pintype "passive"))
    )
    (net (code "60") (name "Net-(DIPSWITCH1-P$1)") (class "Default")
      (node (ref "DIPSWITCH1") (pin "B1") (pinfunction "P$1_B1") (pintype "bidirectional"))
      (node (ref "R2") (pin "1") (pinfunction "1_1") (pintype "passive"))
    )
    (net (code "61") (name "Net-(DIPSWITCH1-P$2)") (class "Default")
      (node (ref "DIPSWITCH1") (pin "B2") (pinfunction "P$2_B2") (pintype "bidirectional"))
      (node (ref "R3") (pin "1") (pinfunction "1_1") (pintype "passive"))
    )
    (net (code "62") (name "Net-(DIPSWITCH1-P$3)") (class "Default")
      (node (ref "DIPSWITCH1") (pin "B3") (pinfunction "P$3_B3") (pintype "bidirectional"))
      (node (ref "R4") (pin "1") (pinfunction "1_1") (pintype "passive"))
    )
    (net (code "63") (name "Net-(DIPSWITCH1-P$4)") (class "Default")
      (node (ref "DIPSWITCH1") (pin "B4") (pinfunction "P$4_B4") (pintype "bidirectional"))
      (node (ref "R5") (pin "1") (pinfunction "1_1") (pintype "passive"))
    )
    (net (code "64") (name "Net-(DIPSWITCH2-P$1)") (class "Default")
      (node (ref "DIPSWITCH2") (pin "B1") (pinfunction "P$1_B1") (pintype "bidirectional"))
      (node (ref "R7") (pin "1") (pinfunction "1_1") (pintype "passive"))
    )
    (net (code "65") (name "Net-(DIPSWITCH2-P$2)") (class "Default")
      (node (ref "DIPSWITCH2") (pin "B2") (pinfunction "P$2_B2") (pintype "bidirectional"))
      (node (ref "R8") (pin "1") (pinfunction "1_1") (pintype "passive"))
    )
    (net (code "66") (name "Net-(DIPSWITCH2-P$3)") (class "Default")
      (node (ref "DIPSWITCH2") (pin "B3") (pinfunction "P$3_B3") (pintype "bidirectional"))
      (node (ref "R9") (pin "1") (pinfunction "1_1") (pintype "passive"))
    )
    (net (code "67") (name "Net-(DIPSWITCH2-P$4)") (class "Default")
      (node (ref "DIPSWITCH2") (pin "B4") (pinfunction "P$4_B4") (pintype "bidirectional"))
      (node (ref "R10") (pin "1") (pinfunction "1_1") (pintype "passive"))
    )
    (net (code "68") (name "Net-(IC1A-BOOT0)") (class "Default")
      (node (ref "IC1") (pin "60") (pinfunction "BOOT0_60") (pintype "input"))
      (node (ref "R25") (pin "2") (pinfunction "2_2") (pintype "passive"))
    )
    (net (code "69") (name "Net-(IC1A-OSC_IN)") (class "Default")
      (node (ref "C15") (pin "1") (pinfunction "1_1") (pintype "passive"))
      (node (ref "IC1") (pin "5") (pinfunction "OSC_IN_5") (pintype "bidirectional"))
      (node (ref "Q2") (pin "2") (pinfunction "2_2") (pintype "passive"))
    )
    (net (code "70") (name "Net-(IC1A-OSC_OUT)") (class "Default")
      (node (ref "C16") (pin "1") (pinfunction "1_1") (pintype "passive"))
      (node (ref "IC1") (pin "6") (pinfunction "OSC_OUT_6") (pintype "bidirectional"))
      (node (ref "Q2") (pin "1") (pinfunction "1_1") (pintype "passive"))
    )
    (net (code "71") (name "Net-(IC1A-VCAP1)") (class "Default")
      (node (ref "C8") (pin "1") (pinfunction "1_1") (pintype "passive"))
      (node (ref "IC1") (pin "30") (pinfunction "VCAP1_30") (pintype "power_in"))
    )
    (net (code "72") (name "Net-(LED_GREEN-Pad1)") (class "Default")
      (node (ref "LED_GREEN") (pin "1") (pinfunction "1_1") (pintype "bidirectional"))
      (node (ref "R27") (pin "1") (pinfunction "1_1") (pintype "passive"))
    )
    (net (code "73") (name "Net-(LED_RED-Pad1)") (class "Default")
      (node (ref "LED_RED") (pin "1") (pinfunction "1_1") (pintype "bidirectional"))
      (node (ref "R28") (pin "1") (pinfunction "1_1") (pintype "passive"))
    )
    (net (code "74") (name "Net-(LED_YELLOW-Pad1)") (class "Default")
      (node (ref "LED_YELLOW") (pin "1") (pinfunction "1_1") (pintype "bidirectional"))
      (node (ref "R26") (pin "1") (pinfunction "1_1") (pintype "passive"))
    )
    (net (code "75") (name "Net-(LM2674-5V-BUCK1-1-CB)") (class "Default")
      (node (ref "C7") (pin "1") (pinfunction "1_1") (pintype "passive"))
      (node (ref "LM2674-5V-BUCK1") (pin "1") (pinfunction "1-CB_1") (pintype "bidirectional"))
    )
    (net (code "76") (name "Net-(LM2674-5V-BUCK1-7-VIN)") (class "Default")
      (node (ref "C-2") (pin "+") (pinfunction "+_+") (pintype "bidirectional"))
      (node (ref "LM2674-5V-BUCK1") (pin "7") (pinfunction "7-VIN_7") (pintype "bidirectional"))
      (node (ref "R23") (pin "2") (pinfunction "2_2") (pintype "passive"))
      (node (ref "SCHOTTY-SS12-2") (pin "-") (pinfunction "-_-") (pintype "bidirectional"))
      (node (ref "SKRUVPLINT_2P5") (pin "3") (pinfunction "P$1_3") (pintype "bidirectional"))
      (node (ref "U$3") (pin "SOURCE") (pinfunction "SOURCE_SOURCE") (pintype "bidirectional"))
    )
    (net (code "77") (name "Net-(LM2674-5V-BUCK1-8-VSW)") (class "Default")
      (node (ref "C7") (pin "2") (pinfunction "2_2") (pintype "passive"))
      (node (ref "L-1") (pin "1") (pinfunction "1_1") (pintype "bidirectional"))
      (node (ref "LM2674-5V-BUCK1") (pin "8") (pinfunction "8-VSW_8") (pintype "bidirectional"))
      (node (ref "SCHOTTY-SS12-1") (pin "-") (pinfunction "-_-") (pintype "bidirectional"))
    )
    (net (code "78") (name "Net-(R1-Pad1)") (class "Default")
      (node (ref "R1") (pin "1") (pinfunction "1_1") (pintype "passive"))
      (node (ref "SMDLED1") (pin "1") (pinfunction "1_1") (pintype "bidirectional"))
    )
    (net (code "79") (name "Net-(R6-Pad1)") (class "Default")
      (node (ref "R6") (pin "1") (pinfunction "1_1") (pintype "passive"))
      (node (ref "SMDLED2") (pin "1") (pinfunction "1_1") (pintype "bidirectional"))
    )
    (net (code "80") (name "Net-(R20-Pad2)") (class "Default")
      (node (ref "R20") (pin "2") (pinfunction "2_2") (pintype "passive"))
      (node (ref "U$3") (pin "DRAIN") (pinfunction "DRAIN_DRAIN") (pintype "bidirectional"))
    )
    (net (code "81") (name "Net-(R22-Pad2)") (class "Default")
      (node (ref "R22") (pin "2") (pinfunction "2_2") (pintype "passive"))
      (node (ref "U$4") (pin "GATE") (pinfunction "GATE_GATE") (pintype "bidirectional"))
    )
    (net (code "82") (name "Net-(R23-Pad1)") (class "Default")
      (node (ref "R23") (pin "1") (pinfunction "1_1") (pintype "passive"))
      (node (ref "U$3") (pin "GATE") (pinfunction "GATE_GATE") (pintype "bidirectional"))
      (node (ref "U$4") (pin "DRAIN") (pinfunction "DRAIN_DRAIN") (pintype "bidirectional"))
    )
    (net (code "83") (name "Net-(U$1-1IN+)") (class "Default")
      (node (ref "R32") (pin "2") (pinfunction "2_2") (pintype "passive"))
      (node (ref "U$1") (pin "P$3") (pinfunction "1IN+_P$3") (pintype "bidirectional"))
    )
    (net (code "84") (name "Net-(U$1-1IN-)") (class "Default")
      (node (ref "U$1") (pin "P$2") (pinfunction "1IN-_P$2") (pintype "bidirectional"))
      (node (ref "U$1") (pin "P$6") (pinfunction "2IN-_P$6") (pintype "bidirectional"))
      (node (ref "U$2") (pin "P$2_B") (pinfunction "P$2_B_P$2_B") (pintype "bidirectional"))
    )
    (net (code "85") (name "Net-(U$1-1OUT)") (class "Default")
      (node (ref "R11") (pin "2") (pinfunction "2_2") (pintype "passive"))
      (node (ref "R33") (pin "1") (pinfunction "1_1") (pintype "passive"))
      (node (ref "U$1") (pin "P$1") (pinfunction "1OUT_P$1") (pintype "bidirectional"))
    )
    (net (code "86") (name "Net-(U$1-2IN+)") (class "Default")
      (node (ref "R34") (pin "1") (pinfunction "1_1") (pintype "passive"))
      (node (ref "U$1") (pin "P$5") (pinfunction "2IN+_P$5") (pintype "bidirectional"))
    )
    (net (code "87") (name "Net-(U$1-2OUT)") (class "Default")
      (node (ref "R12") (pin "1") (pinfunction "1_1") (pintype "passive"))
      (node (ref "R35") (pin "2") (pinfunction "2_2") (pintype "passive"))
      (node (ref "U$1") (pin "P$7") (pinfunction "2OUT_P$7") (pintype "bidirectional"))
    )
    (net (code "88") (name "Net-(U1-AUX_CL)") (class "Default")
      (node (ref "R18") (pin "1") (pinfunction "1_1") (pintype "passive"))
      (node (ref "U1") (pin "7") (pinfunction "AUX_CL_7") (pintype "output"))
    )
    (net (code "89") (name "Net-(U1-AUX_DA)") (class "Default")
      (node (ref "R19") (pin "1") (pinfunction "1_1") (pintype "passive"))
      (node (ref "U1") (pin "21") (pinfunction "AUX_DA_21") (pintype "output"))
    )
    (net (code "90") (name "Net-(U1-REGOUT)") (class "Default")
      (node (ref "C6") (pin "1") (pinfunction "1_1") (pintype "passive"))
      (node (ref "U1") (pin "10") (pinfunction "REGOUT_10") (pintype "passive"))
    )
    (net (code "91") (name "Net-(U2-GPIO6)") (class "Default")
      (node (ref "R29") (pin "1") (pinfunction "1_1") (pintype "passive"))
      (node (ref "U2") (pin "7") (pinfunction "GPIO6_7") (pintype "input"))
    )
    (net (code "92") (name "Net-(U2-I2C_CLK)") (class "Default")
      (node (ref "R31") (pin "1") (pinfunction "1_1") (pintype "passive"))
      (node (ref "U2") (pin "17") (pinfunction "I2C_CLK_17") (pintype "bidirectional"))
    )
    (net (code "93") (name "Net-(U2-I2C_DIO)") (class "Default")
      (node (ref "R30") (pin "1") (pinfunction "1_1") (pintype "passive"))
      (node (ref "U2") (pin "18") (pinfunction "I2C_DIO_18") (pintype "bidirectional"))
    )
    (net (code "94") (name "unconnected-(BT1-2_SPI_MOSI-Pad2)") (class "Default")
      (node (ref "BT1") (pin "2") (pinfunction "2_SPI_MOSI_2") (pintype "bidirectional"))
    )
    (net (code "95") (name "unconnected-(BT1-6_SPI_CLOCK-Pad6)") (class "Default")
      (node (ref "BT1") (pin "6") (pinfunction "6_SPI_CLOCK_6") (pintype "bidirectional"))
    )
    (net (code "96") (name "unconnected-(BT1-7_PCM_CLK-Pad7)") (class "Default")
      (node (ref "BT1") (pin "7") (pinfunction "7_PCM_CLK_7") (pintype "bidirectional"))
    )
    (net (code "97") (name "unconnected-(BT1-8_PCM_CLK-Pad8)") (class "Default")
      (node (ref "BT1") (pin "8") (pinfunction "8_PCM_CLK_8") (pintype "bidirectional"))
    )
    (net (code "98") (name "unconnected-(BT1-9_PCM_IN-Pad9)") (class "Default")
      (node (ref "BT1") (pin "9") (pinfunction "9_PCM_IN_9") (pintype "bidirectional"))
    )
    (net (code "99") (name "unconnected-(BT1-10_PCM_OUT-Pad10)") (class "Default")
      (node (ref "BT1") (pin "10") (pinfunction "10_PCM_OUT_10") (pintype "bidirectional"))
    )
    (net (code "100") (name "unconnected-(BT1-23_SPI_CSB-Pad23)") (class "Default")
      (node (ref "BT1") (pin "23") (pinfunction "23_SPI_CSB_23") (pintype "bidirectional"))
    )
    (net (code "101") (name "unconnected-(BT1-24_SPI_MISO-Pad24)") (class "Default")
      (node (ref "BT1") (pin "24") (pinfunction "24_SPI_MISO_24") (pintype "bidirectional"))
    )
    (net (code "102") (name "unconnected-(BT1-Pad30)") (class "Default")
      (node (ref "BT1") (pin "30") (pinfunction "30_30") (pintype "bidirectional"))
    )
    (net (code "103") (name "unconnected-(BT1-Pad35)") (class "Default")
      (node (ref "BT1") (pin "35") (pinfunction "35_35") (pintype "bidirectional"))
    )
    (net (code "104") (name "unconnected-(BT2-2_SPI_MOSI-Pad2)") (class "Default")
      (node (ref "BT2") (pin "2") (pinfunction "2_SPI_MOSI_2") (pintype "bidirectional"))
    )
    (net (code "105") (name "unconnected-(BT2-6_SPI_CLOCK-Pad6)") (class "Default")
      (node (ref "BT2") (pin "6") (pinfunction "6_SPI_CLOCK_6") (pintype "bidirectional"))
    )
    (net (code "106") (name "unconnected-(BT2-7_PCM_CLK-Pad7)") (class "Default")
      (node (ref "BT2") (pin "7") (pinfunction "7_PCM_CLK_7") (pintype "bidirectional"))
    )
    (net (code "107") (name "unconnected-(BT2-8_PCM_CLK-Pad8)") (class "Default")
      (node (ref "BT2") (pin "8") (pinfunction "8_PCM_CLK_8") (pintype "bidirectional"))
    )
    (net (code "108") (name "unconnected-(BT2-9_PCM_IN-Pad9)") (class "Default")
      (node (ref "BT2") (pin "9") (pinfunction "9_PCM_IN_9") (pintype "bidirectional"))
    )
    (net (code "109") (name "unconnected-(BT2-10_PCM_OUT-Pad10)") (class "Default")
      (node (ref "BT2") (pin "10") (pinfunction "10_PCM_OUT_10") (pintype "bidirectional"))
    )
    (net (code "110") (name "unconnected-(BT2-23_SPI_CSB-Pad23)") (class "Default")
      (node (ref "BT2") (pin "23") (pinfunction "23_SPI_CSB_23") (pintype "bidirectional"))
    )
    (net (code "111") (name "unconnected-(BT2-24_SPI_MISO-Pad24)") (class "Default")
      (node (ref "BT2") (pin "24") (pinfunction "24_SPI_MISO_24") (pintype "bidirectional"))
    )
    (net (code "112") (name "unconnected-(BT2-Pad30)") (class "Default")
      (node (ref "BT2") (pin "30") (pinfunction "30_30") (pintype "bidirectional"))
    )
    (net (code "113") (name "unconnected-(BT2-Pad35)") (class "Default")
      (node (ref "BT2") (pin "35") (pinfunction "35_35") (pintype "bidirectional"))
    )
    (net (code "114") (name "unconnected-(IC1A-PA0-WKUP-Pad14)") (class "Default")
      (node (ref "IC1") (pin "14") (pinfunction "PA0-WKUP_14") (pintype "bidirectional"))
    )
    (net (code "115") (name "unconnected-(IC1A-PA1-Pad15)") (class "Default")
      (node (ref "IC1") (pin "15") (pinfunction "PA1_15") (pintype "bidirectional"))
    )
    (net (code "116") (name "unconnected-(IC1A-PA15-Pad50)") (class "Default")
      (node (ref "IC1") (pin "50") (pinfunction "PA15_50") (pintype "bidirectional"))
    )
    (net (code "117") (name "unconnected-(IC1A-PB4-Pad56)") (class "Default")
      (node (ref "IC1") (pin "56") (pinfunction "PB4_56") (pintype "bidirectional"))
    )
    (net (code "118") (name "unconnected-(IC1A-PB5-Pad57)") (class "Default")
      (node (ref "IC1") (pin "57") (pinfunction "PB5_57") (pintype "bidirectional"))
    )
    (net (code "119") (name "unconnected-(IC1A-PB6-Pad58)") (class "Default")
      (node (ref "IC1") (pin "58") (pinfunction "PB6_58") (pintype "bidirectional"))
    )
    (net (code "120") (name "unconnected-(IC1A-PB7-Pad59)") (class "Default")
      (node (ref "IC1") (pin "59") (pinfunction "PB7_59") (pintype "bidirectional"))
    )
    (net (code "121") (name "unconnected-(IC1A-PB8-Pad61)") (class "Default")
      (node (ref "IC1") (pin "61") (pinfunction "PB8_61") (pintype "bidirectional"))
    )
    (net (code "122") (name "unconnected-(IC1A-PB9-Pad62)") (class "Default")
      (node (ref "IC1") (pin "62") (pinfunction "PB9_62") (pintype "bidirectional"))
    )
    (net (code "123") (name "unconnected-(IC1A-PB10-Pad29)") (class "Default")
      (node (ref "IC1") (pin "29") (pinfunction "PB10_29") (pintype "bidirectional"))
    )
    (net (code "124") (name "unconnected-(IC1A-PB12-Pad33)") (class "Default")
      (node (ref "IC1") (pin "33") (pinfunction "PB12_33") (pintype "bidirectional"))
    )
    (net (code "125") (name "unconnected-(IC1A-PC1-Pad9)") (class "Default")
      (node (ref "IC1") (pin "9") (pinfunction "PC1_9") (pintype "bidirectional"))
    )
    (net (code "126") (name "unconnected-(IC1A-PC13-Pad2)") (class "Default")
      (node (ref "IC1") (pin "2") (pinfunction "PC13_2") (pintype "bidirectional"))
    )
    (net (code "127") (name "unconnected-(IC1A-PC14-Pad3)") (class "Default")
      (node (ref "IC1") (pin "3") (pinfunction "PC14_3") (pintype "bidirectional"))
    )
    (net (code "128") (name "unconnected-(IC1A-PC15-Pad4)") (class "Default")
      (node (ref "IC1") (pin "4") (pinfunction "PC15_4") (pintype "bidirectional"))
    )
    (net (code "129") (name "unconnected-(IC1A-PD2-Pad54)") (class "Default")
      (node (ref "IC1") (pin "54") (pinfunction "PD2_54") (pintype "bidirectional"))
    )
    (net (code "130") (name "unconnected-(LM2674-5V-BUCK1-2-*-Pad2)") (class "Default")
      (node (ref "LM2674-5V-BUCK1") (pin "2") (pinfunction "2-*_2") (pintype "bidirectional"))
    )
    (net (code "131") (name "unconnected-(LM2674-5V-BUCK1-3-*-Pad3)") (class "Default")
      (node (ref "LM2674-5V-BUCK1") (pin "3") (pinfunction "3-*_3") (pintype "bidirectional"))
    )
    (net (code "132") (name "unconnected-(LM2674-5V-BUCK1-5-ON{slash}OFF-Pad5)") (class "Default")
      (node (ref "LM2674-5V-BUCK1") (pin "5") (pinfunction "5-ON/OFF_5") (pintype "bidirectional"))
    )
    (net (code "133") (name "unconnected-(U2-ANT_EXT-Pad10)") (class "Default")
      (node (ref "U2") (pin "10") (pinfunction "ANT_EXT_10") (pintype "input"))
    )
    (net (code "134") (name "unconnected-(U2-ANT_SW-Pad12)") (class "Default")
      (node (ref "U2") (pin "12") (pinfunction "ANT_SW_12") (pintype "input"))
    )
    (net (code "135") (name "unconnected-(U2-GPIO4-Pad15)") (class "Default")
      (node (ref "U2") (pin "15") (pinfunction "GPIO4_15") (pintype "input"))
    )
    (net (code "136") (name "unconnected-(U2-GPIO7-Pad8)") (class "Default")
      (node (ref "U2") (pin "8") (pinfunction "GPIO7_8") (pintype "input"))
    )
    (net (code "137") (name "unconnected-(U2-HOST_I2C_CLK-Pad14)") (class "Default")
      (node (ref "U2") (pin "14") (pinfunction "HOST_I2C_CLK_14") (pintype "bidirectional"))
    )
    (net (code "138") (name "unconnected-(U2-NC{slash}GPIO2-Pad13)") (class "Default")
      (node (ref "U2") (pin "13") (pinfunction "NC/GPIO2_13") (pintype "bidirectional"))
    )
    (net (code "139") (name "unconnected-(U2-NC{slash}GPIO3-Pad2)") (class "Default")
      (node (ref "U2") (pin "2") (pinfunction "NC/GPIO3_2") (pintype "bidirectional"))
    )
    (net (code "140") (name "unconnected-(U2-TM_GPIO5-Pad16)") (class "Default")
      (node (ref "U2") (pin "16") (pinfunction "TM_GPIO5_16") (pintype "output"))
    )
    (net (code "141") (name "unconnected-(U2-WAKEUP-Pad4)") (class "Default")
      (node (ref "U2") (pin "4") (pinfunction "WAKEUP_4") (pintype "output"))
    )
  )
)
